# SCH_Pg2_Cell_Bank.net
KiCad netlist of a schematic drawn in Altium Designer
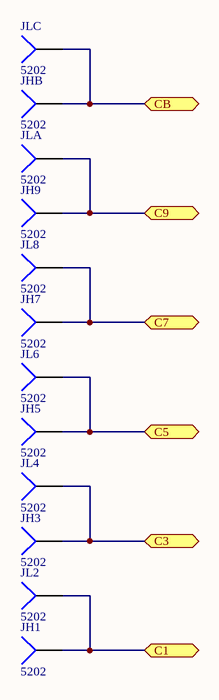
[diagram p0: SCH Pg2 Cell Bank.SchDoc]

(export (version "E")
  (design (tool "Eeschema 10.0.6"))
  (components
    (comp (ref "JH1")
      (value "5202")
      (footprint "BAT-KS5202-PTH")
      (description "Hardware, Battery Contact Spring, PCB-mount")
      (libsource (lib "LIB SCH Master") (part "KS5202"))
    )
    (comp (ref "JH3")
      (value "5202")
      (footprint "BAT-KS5202-PTH")
      (description "Hardware, Battery Contact Spring, PCB-mount")
      (libsource (lib "LIB SCH Master") (part "KS5202"))
    )
    (comp (ref "JH5")
      (value "5202")
      (footprint "BAT-KS5202-PTH")
      (description "Hardware, Battery Contact Spring, PCB-mount")
      (libsource (lib "LIB SCH Master") (part "KS5202"))
    )
    (comp (ref "JH7")
      (value "5202")
      (footprint "BAT-KS5202-PTH")
      (description "Hardware, Battery Contact Spring, PCB-mount")
      (libsource (lib "LIB SCH Master") (part "KS5202"))
    )
    (comp (ref "JH9")
      (value "5202")
      (footprint "BAT-KS5202-PTH")
      (description "Hardware, Battery Contact Spring, PCB-mount")
      (libsource (lib "LIB SCH Master") (part "KS5202"))
    )
    (comp (ref "JHB")
      (value "5202")
      (footprint "BAT-KS5202-PTH")
      (description "Hardware, Battery Contact Spring, PCB-mount")
      (libsource (lib "LIB SCH Master") (part "KS5202"))
    )
    (comp (ref "JL2")
      (value "5202")
      (footprint "BAT-KS5202-PTH")
      (description "Hardware, Battery Contact Spring, PCB-mount")
      (libsource (lib "LIB SCH Master") (part "KS5202"))
    )
    (comp (ref "JL4")
      (value "5202")
      (footprint "BAT-KS5202-PTH")
      (description "Hardware, Battery Contact Spring, PCB-mount")
      (libsource (lib "LIB SCH Master") (part "KS5202"))
    )
    (comp (ref "JL6")
      (value "5202")
      (footprint "BAT-KS5202-PTH")
      (description "Hardware, Battery Contact Spring, PCB-mount")
      (libsource (lib "LIB SCH Master") (part "KS5202"))
    )
    (comp (ref "JL8")
      (value "5202")
      (footprint "BAT-KS5202-PTH")
      (description "Hardware, Battery Contact Spring, PCB-mount")
      (libsource (lib "LIB SCH Master") (part "KS5202"))
    )
    (comp (ref "JLA")
      (value "5202")
      (footprint "BAT-KS5202-PTH")
      (description "Hardware, Battery Contact Spring, PCB-mount")
      (libsource (lib "LIB SCH Master") (part "KS5202"))
    )
    (comp (ref "JLC")
      (value "5202")
      (footprint "BAT-KS5202-PTH")
      (description "Hardware, Battery Contact Spring, PCB-mount")
      (libsource (lib "LIB SCH Master") (part "KS5202"))
    )
  )
  (nets
    (net (code "1") (name "/C1") (class "Default")
      (node (ref "JH1") (pin "1") (pinfunction "1_1") (pintype "passive"))
      (node (ref "JL2") (pin "1") (pinfunction "1_1") (pintype "passive"))
    )
    (net (code "2") (name "/C3") (class "Default")
      (node (ref "JH3") (pin "1") (pinfunction "1_1") (pintype "passive"))
      (node (ref "JL4") (pin "1") (pinfunction "1_1") (pintype "passive"))
    )
    (net (code "3") (name "/C5") (class "Default")
      (node (ref "JH5") (pin "1") (pinfunction "1_1") (pintype "passive"))
      (node (ref "JL6") (pin "1") (pinfunction "1_1") (pintype "passive"))
    )
    (net (code "4") (name "/C7") (class "Default")
      (node (ref "JH7") (pin "1") (pinfunction "1_1") (pintype "passive"))
      (node (ref "JL8") (pin "1") (pinfunction "1_1") (pintype "passive"))
    )
    (net (code "5") (name "/C9") (class "Default")
      (node (ref "JH9") (pin "1") (pinfunction "1_1") (pintype "passive"))
      (node (ref "JLA") (pin "1") (pinfunction "1_1") (pintype "passive"))
    )
    (net (code "6") (name "/CB") (class "Default")
      (node (ref "JHB") (pin "1") (pinfunction "1_1") (pintype "passive"))
      (node (ref "JLC") (pin "1") (pinfunction "1_1") (pintype "passive"))
    )
  )
)
